# Cansat2019_1516_Container_v03.net
KiCad netlist of a schematic drawn in EAGLE
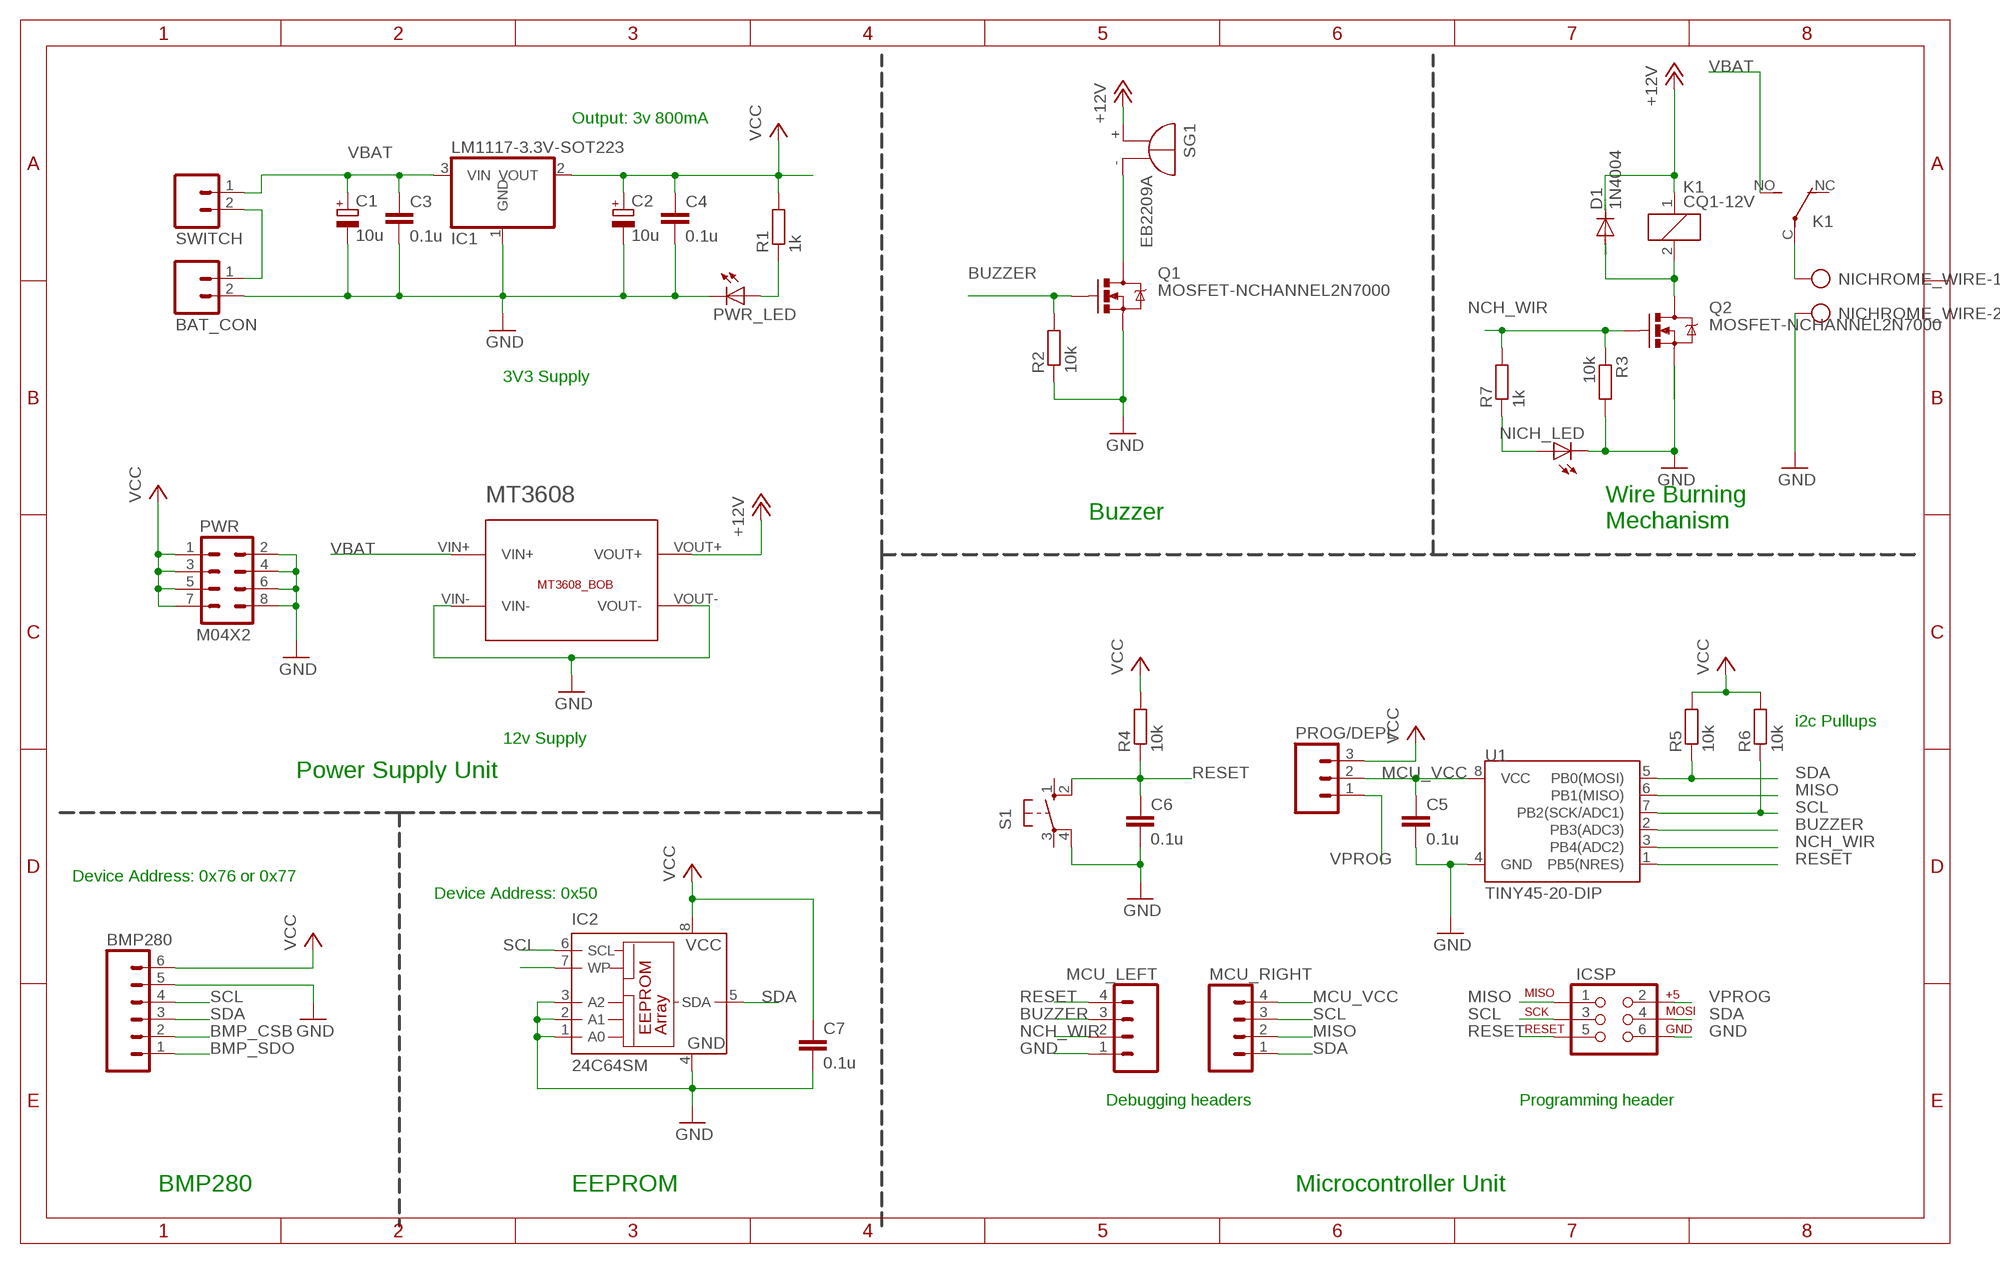
[diagram p0: schematic, sheet 1]

(export (version "E")
  (design (tool "Eeschema 10.0.6"))
  (components
    (comp (ref "BAT_CON")
      (value "M02")
      (footprint "eagle-import:02P")
      (libsource (lib "eagle-import") (part "M02"))
    )
    (comp (ref "BMP280")
      (value "M06")
      (footprint "eagle-import:06P")
      (libsource (lib "eagle-import") (part "M06"))
    )
    (comp (ref "C1")
      (value "10u")
      (footprint "eagle-import:E2,5-6")
      (libsource (lib "eagle-import") (part "CPOL-EUE2.5-6"))
    )
    (comp (ref "C2")
      (value "10u")
      (footprint "eagle-import:E2,5-6")
      (libsource (lib "eagle-import") (part "CPOL-EUE2.5-6"))
    )
    (comp (ref "C3")
      (value "0.1u")
      (footprint "eagle-import:C025-025X050")
      (libsource (lib "eagle-import") (part "C-EU025-025X050"))
    )
    (comp (ref "C4")
      (value "0.1u")
      (footprint "eagle-import:C025-025X050")
      (libsource (lib "eagle-import") (part "C-EU025-025X050"))
    )
    (comp (ref "C5")
      (value "0.1u")
      (footprint "eagle-import:C025-025X050")
      (libsource (lib "eagle-import") (part "C-EU025-025X050"))
    )
    (comp (ref "C6")
      (value "0.1u")
      (footprint "eagle-import:C025-025X050")
      (libsource (lib "eagle-import") (part "C-EU025-025X050"))
    )
    (comp (ref "C7")
      (value "0.1u")
      (footprint "eagle-import:C025-025X050")
      (libsource (lib "eagle-import") (part "C-EU025-025X050"))
    )
    (comp (ref "D1")
      (value "1N4004")
      (footprint "eagle-import:DO41-10")
      (libsource (lib "eagle-import") (part "1N4004"))
    )
    (comp (ref "IC1")
      (value "LM1117-3.3V-SOT223")
      (footprint "eagle-import:SOT223")
      (libsource (lib "eagle-import") (part "LM1117-SOT223-3.3V"))
    )
    (comp (ref "IC2")
      (value "24C64SM")
      (footprint "eagle-import:SO-08M")
      (fields (field (name "MF") "RAMTRON INTERNATIONAL CORP") (field (name "MPN") "FM24C64-S"))
      (libsource (lib "eagle-import") (part "24SMC64"))
    )
    (comp (ref "ICSP")
      (value "AVR_SPI_PRG_6NS")
      (footprint "eagle-import:2X3-NS")
      (libsource (lib "eagle-import") (part "AVR_SPI_PRG_6NS"))
    )
    (comp (ref "K1")
      (value "CQ1-12V")
      (footprint "eagle-import:CQ1")
      (libsource (lib "eagle-import") (part "CQ1-12V"))
    )
    (comp (ref "MCU_LEFT")
      (value "M04")
      (footprint "eagle-import:04P")
      (libsource (lib "eagle-import") (part "M04"))
    )
    (comp (ref "MCU_RIGHT")
      (value "M04")
      (footprint "eagle-import:04P")
      (libsource (lib "eagle-import") (part "M04"))
    )
    (comp (ref "MT3608")
      (value "MT3608_BOB")
      (footprint "eagle-import:MT3608_BOB")
      (libsource (lib "eagle-import") (part "MT3608_BOB"))
    )
    (comp (ref "NICHROME_WIRE")
      (value "AK500/2-H")
      (footprint "eagle-import:AK500_2-H")
      (libsource (lib "eagle-import") (part "AK500/2-H"))
    )
    (comp (ref "NICH_LED")
      (value "LED3MM")
      (footprint "eagle-import:LED3MM")
      (libsource (lib "eagle-import") (part "LED3MM"))
    )
    (comp (ref "PROG/DEPL")
      (value "M03PTH")
      (footprint "eagle-import:1X03")
      (libsource (lib "eagle-import") (part "M03PTH"))
    )
    (comp (ref "PWR")
      (value "M04X2")
      (footprint "eagle-import:2X4")
      (libsource (lib "eagle-import") (part "M04X2"))
    )
    (comp (ref "PWR_LED")
      (value "LED3MM")
      (footprint "eagle-import:LED3MM")
      (libsource (lib "eagle-import") (part "LED3MM"))
    )
    (comp (ref "Q1")
      (value "MOSFET-NCHANNEL2N7000")
      (footprint "eagle-import:TO-92")
      (libsource (lib "eagle-import") (part "MOSFET-NCHANNEL2N7000"))
    )
    (comp (ref "Q2")
      (value "MOSFET-NCHANNEL2N7000")
      (footprint "eagle-import:TO-92")
      (libsource (lib "eagle-import") (part "MOSFET-NCHANNEL2N7000"))
    )
    (comp (ref "R1")
      (value "1k")
      (footprint "eagle-import:0204_7")
      (libsource (lib "eagle-import") (part "R-EU_0204/7"))
    )
    (comp (ref "R2")
      (value "10k")
      (footprint "eagle-import:0204_7")
      (libsource (lib "eagle-import") (part "R-EU_0204/7"))
    )
    (comp (ref "R3")
      (value "10k")
      (footprint "eagle-import:0204_7")
      (libsource (lib "eagle-import") (part "R-EU_0204/7"))
    )
    (comp (ref "R4")
      (value "10k")
      (footprint "eagle-import:0204_7")
      (libsource (lib "eagle-import") (part "R-EU_0204/7"))
    )
    (comp (ref "R5")
      (value "10k")
      (footprint "eagle-import:0204_7")
      (libsource (lib "eagle-import") (part "R-EU_0204/7"))
    )
    (comp (ref "R6")
      (value "10k")
      (footprint "eagle-import:0204_7")
      (libsource (lib "eagle-import") (part "R-EU_0204/7"))
    )
    (comp (ref "R7")
      (value "1k")
      (footprint "eagle-import:0204_7")
      (libsource (lib "eagle-import") (part "R-EU_0204/7"))
    )
    (comp (ref "S1")
      (value "PUSH-BUTTON-6MM")
      (footprint "eagle-import:B3F-10XX")
      (libsource (lib "eagle-import") (part "PUSH-BUTTON-6MM"))
    )
    (comp (ref "SG1")
      (value "EB2209A")
      (footprint "eagle-import:EB2209A")
      (libsource (lib "eagle-import") (part "EB2209A"))
    )
    (comp (ref "SWITCH")
      (value "M02")
      (footprint "eagle-import:02P")
      (libsource (lib "eagle-import") (part "M02"))
    )
    (comp (ref "U1")
      (value "TINY45-20-DIP")
      (footprint "eagle-import:DIP08")
      (libsource (lib "eagle-import") (part "ATTINY45TINY45-20-DIP"))
    )
  )
  (nets
    (net (code "1") (name "+12V") (class "Default")
      (node (ref "D1") (pin "C") (pinfunction "C_C") (pintype "passive"))
      (node (ref "K1") (pin "1") (pinfunction "1_1") (pintype "passive"))
      (node (ref "MT3608") (pin "VOUT+") (pinfunction "VOUT+_VOUT+") (pintype "bidirectional"))
      (node (ref "SG1") (pin "+") (pinfunction "+_+") (pintype "passive"))
    )
    (net (code "2") (name "/BMP_CSB") (class "Default")
      (node (ref "BMP280") (pin "2") (pinfunction "2_2") (pintype "passive"))
    )
    (net (code "3") (name "/BMP_SDO") (class "Default")
      (node (ref "BMP280") (pin "1") (pinfunction "1_1") (pintype "passive"))
    )
    (net (code "4") (name "/BUZZER") (class "Default")
      (node (ref "MCU_LEFT") (pin "3") (pinfunction "3_3") (pintype "passive"))
      (node (ref "Q1") (pin "2") (pinfunction "G_2") (pintype "passive"))
      (node (ref "R2") (pin "2") (pinfunction "2_2") (pintype "passive"))
      (node (ref "U1") (pin "2") (pinfunction "PB3(ADC3)_2") (pintype "bidirectional"))
    )
    (net (code "5") (name "/MCU_VCC") (class "Default")
      (node (ref "C5") (pin "1") (pinfunction "1_1") (pintype "passive"))
      (node (ref "MCU_RIGHT") (pin "4") (pinfunction "4_4") (pintype "passive"))
      (node (ref "PROG/DEPL") (pin "2") (pinfunction "2_2") (pintype "passive"))
      (node (ref "U1") (pin "8") (pinfunction "VCC_8") (pintype "bidirectional"))
    )
    (net (code "6") (name "/MISO") (class "Default")
      (node (ref "ICSP") (pin "1") (pinfunction "1_1") (pintype "passive"))
      (node (ref "MCU_RIGHT") (pin "2") (pinfunction "2_2") (pintype "passive"))
      (node (ref "U1") (pin "6") (pinfunction "PB1(MISO)_6") (pintype "bidirectional"))
    )
    (net (code "7") (name "/NCH_WIR") (class "Default")
      (node (ref "MCU_LEFT") (pin "2") (pinfunction "2_2") (pintype "passive"))
      (node (ref "Q2") (pin "2") (pinfunction "G_2") (pintype "passive"))
      (node (ref "R3") (pin "1") (pinfunction "1_1") (pintype "passive"))
      (node (ref "R7") (pin "2") (pinfunction "2_2") (pintype "passive"))
      (node (ref "U1") (pin "3") (pinfunction "PB4(ADC2)_3") (pintype "bidirectional"))
    )
    (net (code "8") (name "/RESET") (class "Default")
      (node (ref "C6") (pin "1") (pinfunction "1_1") (pintype "passive"))
      (node (ref "ICSP") (pin "5") (pinfunction "5_5") (pintype "passive"))
      (node (ref "MCU_LEFT") (pin "4") (pinfunction "4_4") (pintype "passive"))
      (node (ref "R4") (pin "1") (pinfunction "1_1") (pintype "passive"))
      (node (ref "S1") (pin "2") (pinfunction "S1_2") (pintype "passive"))
      (node (ref "U1") (pin "1") (pinfunction "PB5(NRES)_1") (pintype "bidirectional"))
    )
    (net (code "9") (name "/SCL") (class "Default")
      (node (ref "BMP280") (pin "4") (pinfunction "4_4") (pintype "passive"))
      (node (ref "IC2") (pin "6") (pinfunction "SCL_6") (pintype "input"))
      (node (ref "ICSP") (pin "3") (pinfunction "3_3") (pintype "passive"))
      (node (ref "MCU_RIGHT") (pin "3") (pinfunction "3_3") (pintype "passive"))
      (node (ref "R6") (pin "1") (pinfunction "1_1") (pintype "passive"))
      (node (ref "U1") (pin "7") (pinfunction "PB2(SCK/ADC1)_7") (pintype "bidirectional"))
    )
    (net (code "10") (name "/SDA") (class "Default")
      (node (ref "BMP280") (pin "3") (pinfunction "3_3") (pintype "passive"))
      (node (ref "IC2") (pin "5") (pinfunction "SDA_5") (pintype "bidirectional"))
      (node (ref "ICSP") (pin "4") (pinfunction "4_4") (pintype "passive"))
      (node (ref "MCU_RIGHT") (pin "1") (pinfunction "1_1") (pintype "passive"))
      (node (ref "R5") (pin "1") (pinfunction "1_1") (pintype "passive"))
      (node (ref "U1") (pin "5") (pinfunction "PB0(MOSI)_5") (pintype "bidirectional"))
    )
    (net (code "11") (name "/VBAT") (class "Default")
      (node (ref "C1") (pin "+") (pinfunction "+_+") (pintype "passive"))
      (node (ref "C3") (pin "1") (pinfunction "1_1") (pintype "passive"))
      (node (ref "IC1") (pin "3") (pinfunction "VIN_3") (pintype "input"))
      (node (ref "K1") (pin "NO") (pinfunction "S_NO") (pintype "passive"))
      (node (ref "MT3608") (pin "VIN+") (pinfunction "VIN+_VIN+") (pintype "bidirectional"))
      (node (ref "SWITCH") (pin "1") (pinfunction "1_1") (pintype "passive"))
    )
    (net (code "12") (name "/VPROG") (class "Default")
      (node (ref "ICSP") (pin "2") (pinfunction "2_2") (pintype "passive"))
      (node (ref "PROG/DEPL") (pin "1") (pinfunction "1_1") (pintype "passive"))
    )
    (net (code "13") (name "GND") (class "Default")
      (node (ref "BAT_CON") (pin "2") (pinfunction "2_2") (pintype "passive"))
      (node (ref "BMP280") (pin "5") (pinfunction "5_5") (pintype "passive"))
      (node (ref "C1") (pin "-") (pinfunction "-_-") (pintype "passive"))
      (node (ref "C2") (pin "-") (pinfunction "-_-") (pintype "passive"))
      (node (ref "C3") (pin "2") (pinfunction "2_2") (pintype "passive"))
      (node (ref "C4") (pin "2") (pinfunction "2_2") (pintype "passive"))
      (node (ref "C5") (pin "2") (pinfunction "2_2") (pintype "passive"))
      (node (ref "C6") (pin "2") (pinfunction "2_2") (pintype "passive"))
      (node (ref "C7") (pin "2") (pinfunction "2_2") (pintype "passive"))
      (node (ref "IC1") (pin "1") (pinfunction "GND_1") (pintype "power_in"))
      (node (ref "IC2") (pin "1") (pinfunction "A0_1") (pintype "input"))
      (node (ref "IC2") (pin "2") (pinfunction "A1_2") (pintype "input"))
      (node (ref "IC2") (pin "3") (pinfunction "A2_3") (pintype "input"))
      (node (ref "IC2") (pin "4") (pinfunction "GND_4") (pintype "power_in"))
      (node (ref "ICSP") (pin "6") (pinfunction "6_6") (pintype "passive"))
      (node (ref "MCU_LEFT") (pin "1") (pinfunction "1_1") (pintype "passive"))
      (node (ref "MT3608") (pin "VIN-") (pinfunction "VIN-_VIN-") (pintype "bidirectional"))
      (node (ref "MT3608") (pin "VOUT-") (pinfunction "VOUT-_VOUT-") (pintype "bidirectional"))
      (node (ref "NICHROME_WIRE") (pin "2") (pinfunction "KL_2") (pintype "passive"))
      (node (ref "NICH_LED") (pin "K") (pinfunction "C_K") (pintype "passive"))
      (node (ref "PWR") (pin "2") (pinfunction "2_2") (pintype "passive"))
      (node (ref "PWR") (pin "4") (pinfunction "4_4") (pintype "passive"))
      (node (ref "PWR") (pin "6") (pinfunction "6_6") (pintype "passive"))
      (node (ref "PWR") (pin "8") (pinfunction "8_8") (pintype "passive"))
      (node (ref "PWR_LED") (pin "K") (pinfunction "C_K") (pintype "passive"))
      (node (ref "Q1") (pin "1") (pinfunction "S_1") (pintype "passive"))
      (node (ref "Q2") (pin "1") (pinfunction "S_1") (pintype "passive"))
      (node (ref "R2") (pin "1") (pinfunction "1_1") (pintype "passive"))
      (node (ref "R3") (pin "2") (pinfunction "2_2") (pintype "passive"))
      (node (ref "S1") (pin "4") (pinfunction "P1_4") (pintype "passive"))
      (node (ref "U1") (pin "4") (pinfunction "GND_4") (pintype "bidirectional"))
    )
    (net (code "14") (name "Net-(BAT_CON-Pad1)") (class "Default")
      (node (ref "BAT_CON") (pin "1") (pinfunction "1_1") (pintype "passive"))
      (node (ref "SWITCH") (pin "2") (pinfunction "2_2") (pintype "passive"))
    )
    (net (code "15") (name "Net-(K1B-P)") (class "Default")
      (node (ref "K1") (pin "C") (pinfunction "P_C") (pintype "passive"))
      (node (ref "NICHROME_WIRE") (pin "1") (pinfunction "KL_1") (pintype "passive"))
    )
    (net (code "16") (name "Net-(NICH_LED-PadA)") (class "Default")
      (node (ref "NICH_LED") (pin "A") (pinfunction "A_A") (pintype "passive"))
      (node (ref "R7") (pin "1") (pinfunction "1_1") (pintype "passive"))
    )
    (net (code "17") (name "Net-(PWR_LED-PadA)") (class "Default")
      (node (ref "PWR_LED") (pin "A") (pinfunction "A_A") (pintype "passive"))
      (node (ref "R1") (pin "1") (pinfunction "1_1") (pintype "passive"))
    )
    (net (code "18") (name "Net-(Q1-D)") (class "Default")
      (node (ref "Q1") (pin "3") (pinfunction "D_3") (pintype "passive"))
      (node (ref "SG1") (pin "-") (pinfunction "-_-") (pintype "passive"))
    )
    (net (code "19") (name "Net-(Q2-D)") (class "Default")
      (node (ref "D1") (pin "A") (pinfunction "A_A") (pintype "passive"))
      (node (ref "K1") (pin "2") (pinfunction "2_2") (pintype "passive"))
      (node (ref "Q2") (pin "3") (pinfunction "D_3") (pintype "passive"))
    )
    (net (code "20") (name "VCC") (class "Default")
      (node (ref "BMP280") (pin "6") (pinfunction "6_6") (pintype "passive"))
      (node (ref "C2") (pin "+") (pinfunction "+_+") (pintype "passive"))
      (node (ref "C4") (pin "1") (pinfunction "1_1") (pintype "passive"))
      (node (ref "C7") (pin "1") (pinfunction "1_1") (pintype "passive"))
      (node (ref "IC1") (pin "2") (pinfunction "VOUT_2") (pintype "output"))
      (node (ref "IC2") (pin "8") (pinfunction "VCC_8") (pintype "power_in"))
      (node (ref "PROG/DEPL") (pin "3") (pinfunction "3_3") (pintype "passive"))
      (node (ref "PWR") (pin "1") (pinfunction "1_1") (pintype "passive"))
      (node (ref "PWR") (pin "3") (pinfunction "3_3") (pintype "passive"))
      (node (ref "PWR") (pin "5") (pinfunction "5_5") (pintype "passive"))
      (node (ref "PWR") (pin "7") (pinfunction "7_7") (pintype "passive"))
      (node (ref "R1") (pin "2") (pinfunction "2_2") (pintype "passive"))
      (node (ref "R4") (pin "2") (pinfunction "2_2") (pintype "passive"))
      (node (ref "R5") (pin "2") (pinfunction "2_2") (pintype "passive"))
      (node (ref "R6") (pin "2") (pinfunction "2_2") (pintype "passive"))
    )
    (net (code "21") (name "unconnected-(IC2-WP-Pad7)") (class "Default")
      (node (ref "IC2") (pin "7") (pinfunction "WP_7") (pintype "input"))
    )
    (net (code "22") (name "unconnected-(K1B-O-PadNC)") (class "Default")
      (node (ref "K1") (pin "NC") (pinfunction "O_NC") (pintype "passive"))
    )
    (net (code "23") (name "unconnected-(S1-P-Pad3)") (class "Default")
      (node (ref "S1") (pin "3") (pinfunction "P_3") (pintype "passive"))
    )
    (net (code "24") (name "unconnected-(S1-S-Pad1)") (class "Default")
      (node (ref "S1") (pin "1") (pinfunction "S_1") (pintype "passive"))
    )
  )
)
